# plaits_5u_ioboard.net
KiCad netlist of a schematic drawn in EAGLE
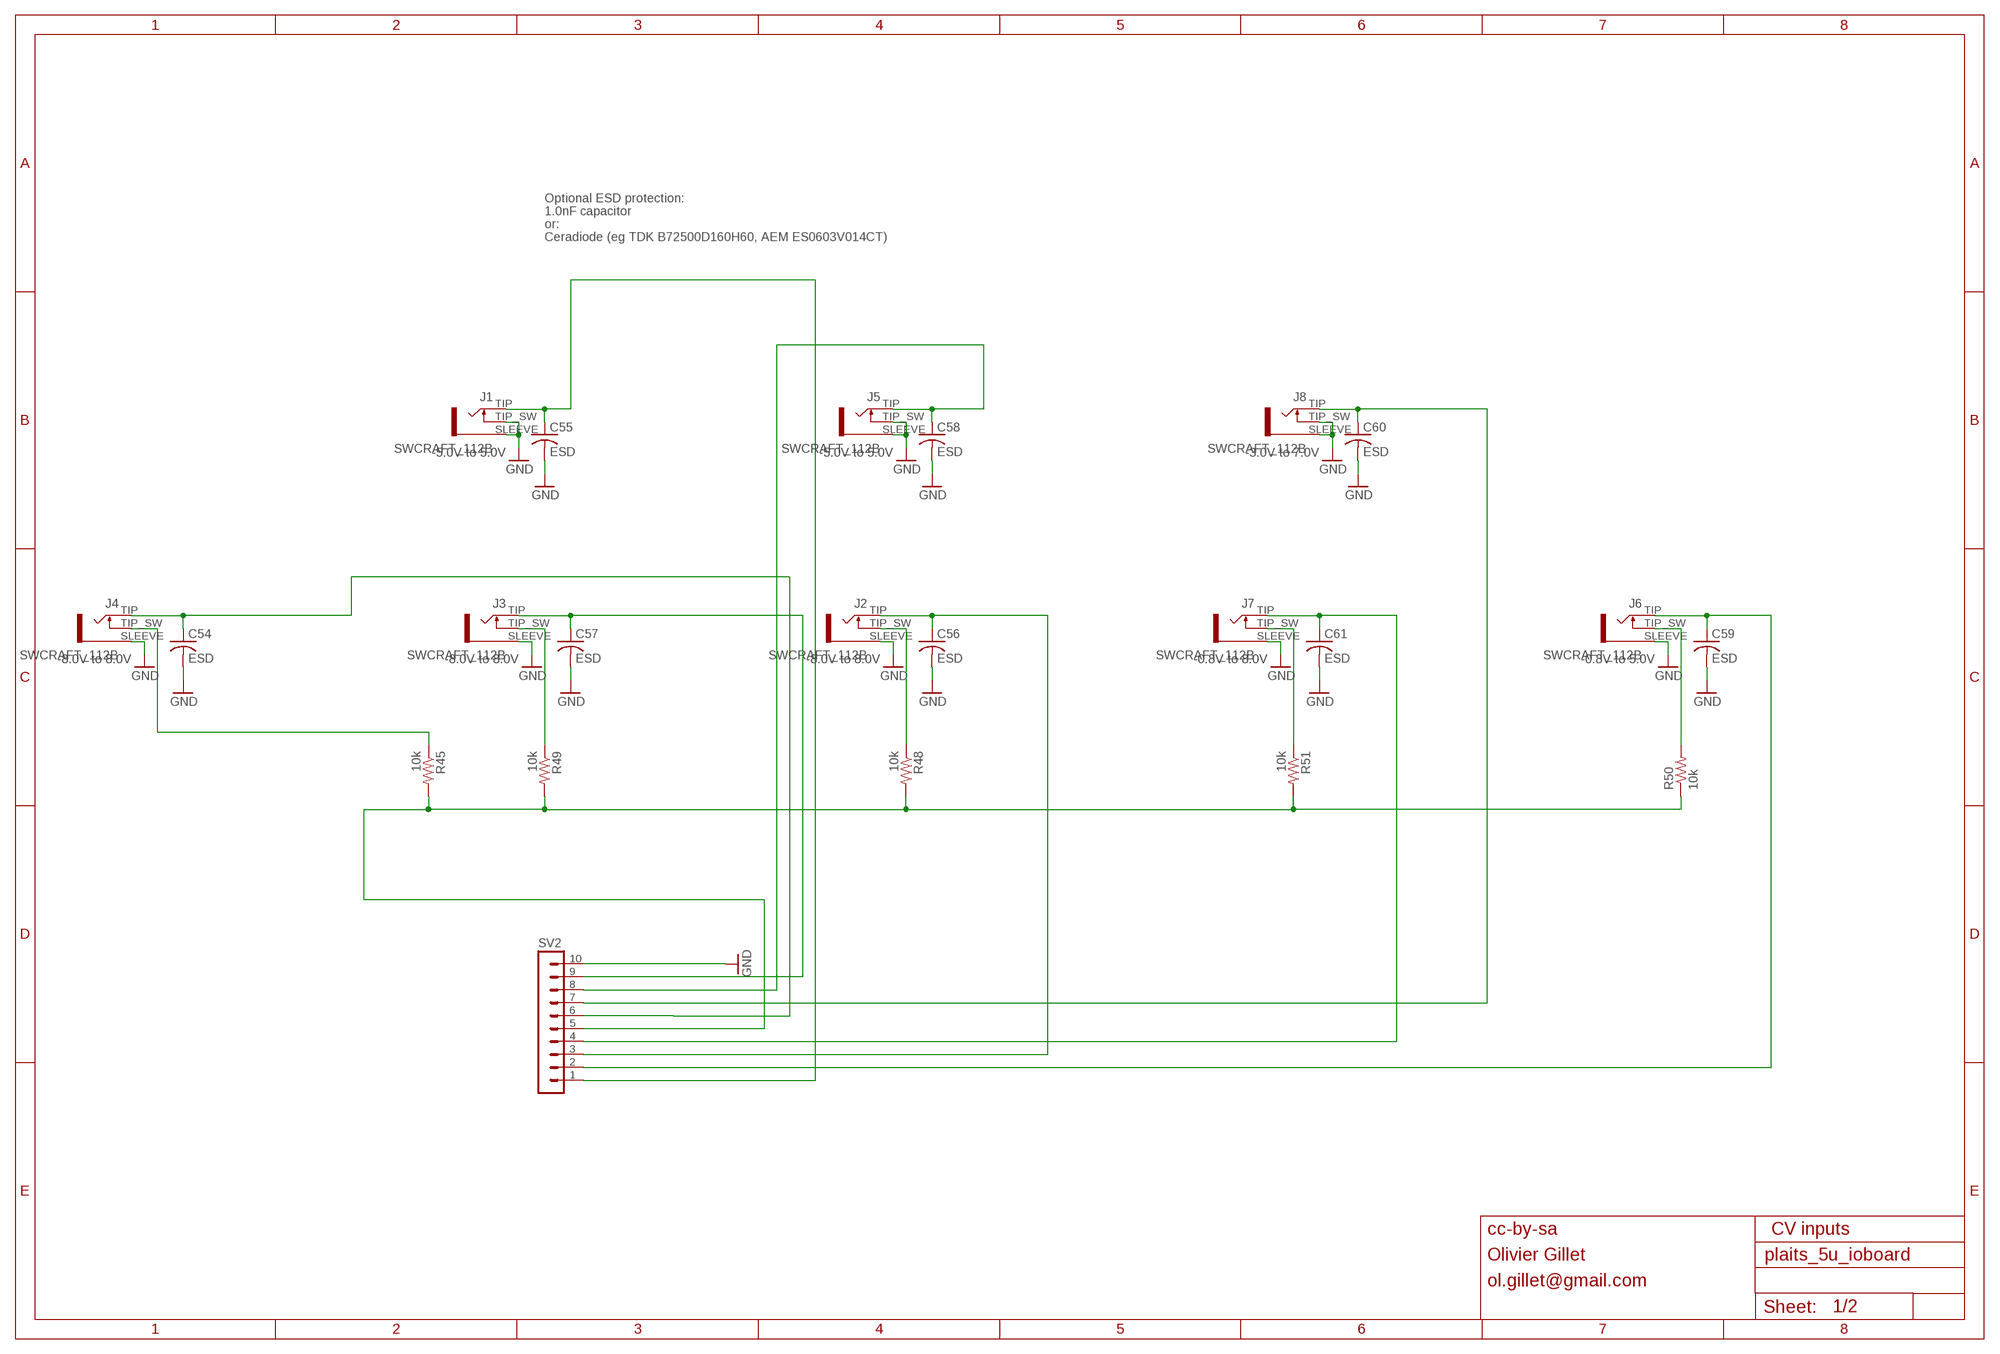
[diagram p0: schematic, sheet 1]
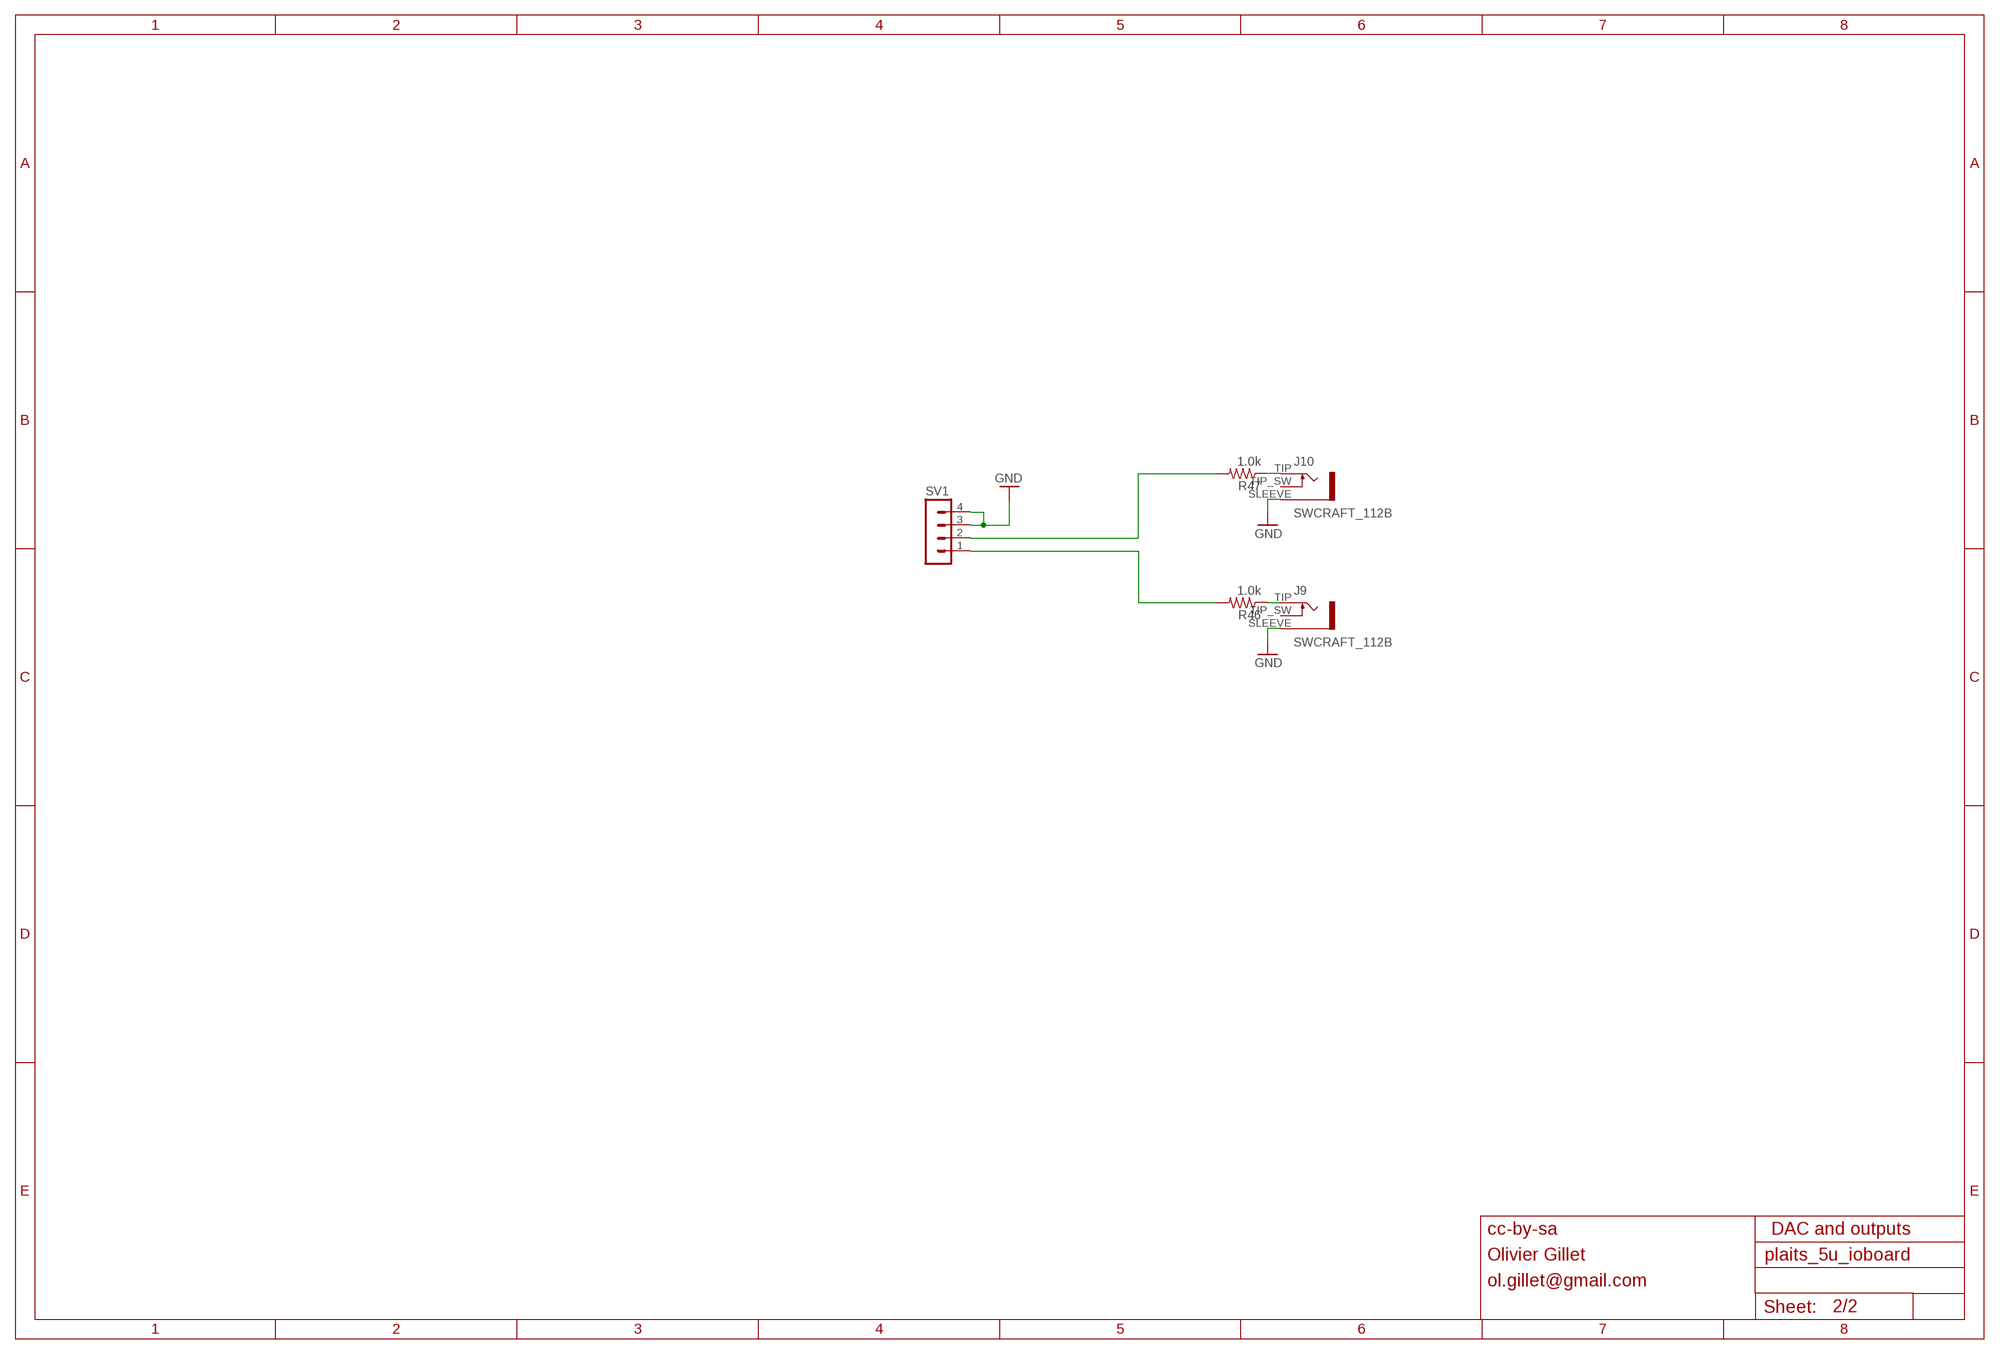
[diagram p1: schematic, sheet 2]

(export (version "E")
  (design (tool "Eeschema 10.0.6"))
  (components
    (comp (ref "J9")
      (value "SWCRAFT_112B")
      (footprint "eagle-import:SWCRAFT_112_SLOTS")
      (libsource (lib "eagle-import") (part "SWCRAFT_112B"))
    )
    (comp (ref "J10")
      (value "SWCRAFT_112B")
      (footprint "eagle-import:SWCRAFT_112_SLOTS")
      (libsource (lib "eagle-import") (part "SWCRAFT_112B"))
    )
    (comp (ref "R46")
      (value "1.0k")
      (footprint "eagle-import:R0805")
      (libsource (lib "eagle-import") (part "R-US_R0805"))
    )
    (comp (ref "R47")
      (value "1.0k")
      (footprint "eagle-import:R0805")
      (libsource (lib "eagle-import") (part "R-US_R0805"))
    )
    (comp (ref "SV1")
      (value "MA04-1")
      (footprint "eagle-import:MA04-1")
      (libsource (lib "eagle-import") (part "MA04-1"))
    )
    (comp (ref "C54")
      (value "ESD")
      (footprint "eagle-import:C0805")
      (libsource (lib "eagle-import") (part "C-USC0805"))
    )
    (comp (ref "C55")
      (value "ESD")
      (footprint "eagle-import:C0805")
      (libsource (lib "eagle-import") (part "C-USC0805"))
    )
    (comp (ref "C56")
      (value "ESD")
      (footprint "eagle-import:C0805")
      (libsource (lib "eagle-import") (part "C-USC0805"))
    )
    (comp (ref "C57")
      (value "ESD")
      (footprint "eagle-import:C0805")
      (libsource (lib "eagle-import") (part "C-USC0805"))
    )
    (comp (ref "C58")
      (value "ESD")
      (footprint "eagle-import:C0805")
      (libsource (lib "eagle-import") (part "C-USC0805"))
    )
    (comp (ref "C59")
      (value "ESD")
      (footprint "eagle-import:C0805")
      (libsource (lib "eagle-import") (part "C-USC0805"))
    )
    (comp (ref "C60")
      (value "ESD")
      (footprint "eagle-import:C0805")
      (libsource (lib "eagle-import") (part "C-USC0805"))
    )
    (comp (ref "C61")
      (value "ESD")
      (footprint "eagle-import:C0805")
      (libsource (lib "eagle-import") (part "C-USC0805"))
    )
    (comp (ref "J1")
      (value "SWCRAFT_112B")
      (footprint "eagle-import:SWCRAFT_112_SLOTS")
      (libsource (lib "eagle-import") (part "SWCRAFT_112B"))
    )
    (comp (ref "J2")
      (value "SWCRAFT_112B")
      (footprint "eagle-import:SWCRAFT_112_SLOTS")
      (libsource (lib "eagle-import") (part "SWCRAFT_112B"))
    )
    (comp (ref "J3")
      (value "SWCRAFT_112B")
      (footprint "eagle-import:SWCRAFT_112_SLOTS")
      (libsource (lib "eagle-import") (part "SWCRAFT_112B"))
    )
    (comp (ref "J4")
      (value "SWCRAFT_112B")
      (footprint "eagle-import:SWCRAFT_112_SLOTS")
      (libsource (lib "eagle-import") (part "SWCRAFT_112B"))
    )
    (comp (ref "J5")
      (value "SWCRAFT_112B")
      (footprint "eagle-import:SWCRAFT_112_SLOTS")
      (libsource (lib "eagle-import") (part "SWCRAFT_112B"))
    )
    (comp (ref "J6")
      (value "SWCRAFT_112B")
      (footprint "eagle-import:SWCRAFT_112_SLOTS")
      (libsource (lib "eagle-import") (part "SWCRAFT_112B"))
    )
    (comp (ref "J7")
      (value "SWCRAFT_112B")
      (footprint "eagle-import:SWCRAFT_112_SLOTS")
      (libsource (lib "eagle-import") (part "SWCRAFT_112B"))
    )
    (comp (ref "J8")
      (value "SWCRAFT_112B")
      (footprint "eagle-import:SWCRAFT_112_SLOTS")
      (libsource (lib "eagle-import") (part "SWCRAFT_112B"))
    )
    (comp (ref "R45")
      (value "10k")
      (footprint "eagle-import:R0805")
      (libsource (lib "eagle-import") (part "R-US_R0805"))
    )
    (comp (ref "R48")
      (value "10k")
      (footprint "eagle-import:R0805")
      (libsource (lib "eagle-import") (part "R-US_R0805"))
    )
    (comp (ref "R49")
      (value "10k")
      (footprint "eagle-import:R0805")
      (libsource (lib "eagle-import") (part "R-US_R0805"))
    )
    (comp (ref "R50")
      (value "10k")
      (footprint "eagle-import:R0805")
      (libsource (lib "eagle-import") (part "R-US_R0805"))
    )
    (comp (ref "R51")
      (value "10k")
      (footprint "eagle-import:R0805")
      (libsource (lib "eagle-import") (part "R-US_R0805"))
    )
    (comp (ref "SV2")
      (value "MA10-1")
      (footprint "eagle-import:MA10-1")
      (libsource (lib "eagle-import") (part "MA10-1"))
    )
  )
  (nets
    (net (code "1") (name "GND") (class "Default")
      (node (ref "C54") (pin "2") (pinfunction "2_2") (pintype "passive"))
      (node (ref "C55") (pin "2") (pinfunction "2_2") (pintype "passive"))
      (node (ref "C56") (pin "2") (pinfunction "2_2") (pintype "passive"))
      (node (ref "C57") (pin "2") (pinfunction "2_2") (pintype "passive"))
      (node (ref "C58") (pin "2") (pinfunction "2_2") (pintype "passive"))
      (node (ref "C59") (pin "2") (pinfunction "2_2") (pintype "passive"))
      (node (ref "C60") (pin "2") (pinfunction "2_2") (pintype "passive"))
      (node (ref "C61") (pin "2") (pinfunction "2_2") (pintype "passive"))
      (node (ref "J1") (pin "SLEEVE") (pinfunction "5_SLEEVE") (pintype "passive"))
      (node (ref "J1") (pin "TIP_SW") (pinfunction "4_TIP_SW") (pintype "passive"))
      (node (ref "J10") (pin "SLEEVE") (pinfunction "5_SLEEVE") (pintype "passive"))
      (node (ref "J2") (pin "SLEEVE") (pinfunction "5_SLEEVE") (pintype "passive"))
      (node (ref "J3") (pin "SLEEVE") (pinfunction "5_SLEEVE") (pintype "passive"))
      (node (ref "J4") (pin "SLEEVE") (pinfunction "5_SLEEVE") (pintype "passive"))
      (node (ref "J5") (pin "SLEEVE") (pinfunction "5_SLEEVE") (pintype "passive"))
      (node (ref "J5") (pin "TIP_SW") (pinfunction "4_TIP_SW") (pintype "passive"))
      (node (ref "J6") (pin "SLEEVE") (pinfunction "5_SLEEVE") (pintype "passive"))
      (node (ref "J7") (pin "SLEEVE") (pinfunction "5_SLEEVE") (pintype "passive"))
      (node (ref "J8") (pin "SLEEVE") (pinfunction "5_SLEEVE") (pintype "passive"))
      (node (ref "J8") (pin "TIP_SW") (pinfunction "4_TIP_SW") (pintype "passive"))
      (node (ref "J9") (pin "SLEEVE") (pinfunction "5_SLEEVE") (pintype "passive"))
      (node (ref "SV1") (pin "3") (pinfunction "3_3") (pintype "passive"))
      (node (ref "SV1") (pin "4") (pinfunction "4_4") (pintype "passive"))
      (node (ref "SV2") (pin "10") (pinfunction "10_10") (pintype "passive"))
    )
    (net (code "2") (name "Net-(J1-3)") (class "Default")
      (node (ref "C55") (pin "1") (pinfunction "1_1") (pintype "passive"))
      (node (ref "J1") (pin "TIP") (pinfunction "3_TIP") (pintype "passive"))
      (node (ref "SV2") (pin "1") (pinfunction "1_1") (pintype "passive"))
    )
    (net (code "3") (name "Net-(J2-3)") (class "Default")
      (node (ref "C56") (pin "1") (pinfunction "1_1") (pintype "passive"))
      (node (ref "J2") (pin "TIP") (pinfunction "3_TIP") (pintype "passive"))
      (node (ref "SV2") (pin "3") (pinfunction "3_3") (pintype "passive"))
    )
    (net (code "4") (name "Net-(J2-4)") (class "Default")
      (node (ref "J2") (pin "TIP_SW") (pinfunction "4_TIP_SW") (pintype "passive"))
      (node (ref "R48") (pin "1") (pinfunction "1_1") (pintype "passive"))
    )
    (net (code "5") (name "Net-(J3-3)") (class "Default")
      (node (ref "C57") (pin "1") (pinfunction "1_1") (pintype "passive"))
      (node (ref "J3") (pin "TIP") (pinfunction "3_TIP") (pintype "passive"))
      (node (ref "SV2") (pin "9") (pinfunction "9_9") (pintype "passive"))
    )
    (net (code "6") (name "Net-(J3-4)") (class "Default")
      (node (ref "J3") (pin "TIP_SW") (pinfunction "4_TIP_SW") (pintype "passive"))
      (node (ref "R49") (pin "1") (pinfunction "1_1") (pintype "passive"))
    )
    (net (code "7") (name "Net-(J4-3)") (class "Default")
      (node (ref "C54") (pin "1") (pinfunction "1_1") (pintype "passive"))
      (node (ref "J4") (pin "TIP") (pinfunction "3_TIP") (pintype "passive"))
      (node (ref "SV2") (pin "6") (pinfunction "6_6") (pintype "passive"))
    )
    (net (code "8") (name "Net-(J4-4)") (class "Default")
      (node (ref "J4") (pin "TIP_SW") (pinfunction "4_TIP_SW") (pintype "passive"))
      (node (ref "R45") (pin "1") (pinfunction "1_1") (pintype "passive"))
    )
    (net (code "9") (name "Net-(J5-3)") (class "Default")
      (node (ref "C58") (pin "1") (pinfunction "1_1") (pintype "passive"))
      (node (ref "J5") (pin "TIP") (pinfunction "3_TIP") (pintype "passive"))
      (node (ref "SV2") (pin "8") (pinfunction "8_8") (pintype "passive"))
    )
    (net (code "10") (name "Net-(J6-3)") (class "Default")
      (node (ref "C59") (pin "1") (pinfunction "1_1") (pintype "passive"))
      (node (ref "J6") (pin "TIP") (pinfunction "3_TIP") (pintype "passive"))
      (node (ref "SV2") (pin "2") (pinfunction "2_2") (pintype "passive"))
    )
    (net (code "11") (name "Net-(J6-4)") (class "Default")
      (node (ref "J6") (pin "TIP_SW") (pinfunction "4_TIP_SW") (pintype "passive"))
      (node (ref "R50") (pin "2") (pinfunction "2_2") (pintype "passive"))
    )
    (net (code "12") (name "Net-(J7-3)") (class "Default")
      (node (ref "C61") (pin "1") (pinfunction "1_1") (pintype "passive"))
      (node (ref "J7") (pin "TIP") (pinfunction "3_TIP") (pintype "passive"))
      (node (ref "SV2") (pin "4") (pinfunction "4_4") (pintype "passive"))
    )
    (net (code "13") (name "Net-(J7-4)") (class "Default")
      (node (ref "J7") (pin "TIP_SW") (pinfunction "4_TIP_SW") (pintype "passive"))
      (node (ref "R51") (pin "1") (pinfunction "1_1") (pintype "passive"))
    )
    (net (code "14") (name "Net-(J8-3)") (class "Default")
      (node (ref "C60") (pin "1") (pinfunction "1_1") (pintype "passive"))
      (node (ref "J8") (pin "TIP") (pinfunction "3_TIP") (pintype "passive"))
      (node (ref "SV2") (pin "7") (pinfunction "7_7") (pintype "passive"))
    )
    (net (code "15") (name "Net-(J9-3)") (class "Default")
      (node (ref "J9") (pin "TIP") (pinfunction "3_TIP") (pintype "passive"))
      (node (ref "R46") (pin "1") (pinfunction "1_1") (pintype "passive"))
    )
    (net (code "16") (name "Net-(J10-3)") (class "Default")
      (node (ref "J10") (pin "TIP") (pinfunction "3_TIP") (pintype "passive"))
      (node (ref "R47") (pin "1") (pinfunction "1_1") (pintype "passive"))
    )
    (net (code "17") (name "Net-(R45-Pad2)") (class "Default")
      (node (ref "R45") (pin "2") (pinfunction "2_2") (pintype "passive"))
      (node (ref "R48") (pin "2") (pinfunction "2_2") (pintype "passive"))
      (node (ref "R49") (pin "2") (pinfunction "2_2") (pintype "passive"))
      (node (ref "R50") (pin "1") (pinfunction "1_1") (pintype "passive"))
      (node (ref "R51") (pin "2") (pinfunction "2_2") (pintype "passive"))
      (node (ref "SV2") (pin "5") (pinfunction "5_5") (pintype "passive"))
    )
    (net (code "18") (name "Net-(R46-Pad2)") (class "Default")
      (node (ref "R46") (pin "2") (pinfunction "2_2") (pintype "passive"))
      (node (ref "SV1") (pin "1") (pinfunction "1_1") (pintype "passive"))
    )
    (net (code "19") (name "Net-(R47-Pad2)") (class "Default")
      (node (ref "R47") (pin "2") (pinfunction "2_2") (pintype "passive"))
      (node (ref "SV1") (pin "2") (pinfunction "2_2") (pintype "passive"))
    )
    (net (code "20") (name "unconnected-(J9-4-PadTIP_SW)") (class "Default")
      (node (ref "J9") (pin "TIP_SW") (pinfunction "4_TIP_SW") (pintype "passive"))
    )
    (net (code "21") (name "unconnected-(J10-4-PadTIP_SW)") (class "Default")
      (node (ref "J10") (pin "TIP_SW") (pinfunction "4_TIP_SW") (pintype "passive"))
    )
  )
)
